# light_digital_sensor.net
KiCad netlist of a schematic drawn in EAGLE
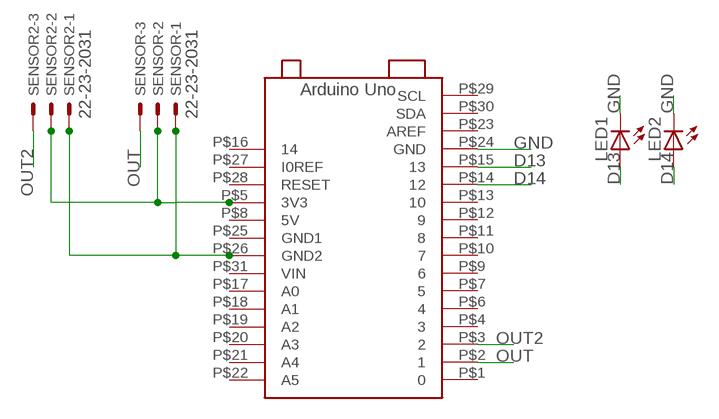
[diagram p0: schematic, sheet 1]

(export (version "E")
  (design (tool "Eeschema 10.0.6"))
  (components
    (comp (ref "LED1")
      (value "LED3MM")
      (footprint "eagle-import:LED3MM")
      (libsource (lib "eagle-import") (part "LED3MM"))
    )
    (comp (ref "LED2")
      (value "LED3MM")
      (footprint "eagle-import:LED3MM")
      (libsource (lib "eagle-import") (part "LED3MM"))
    )
    (comp (ref "SENSOR")
      (value "22-23-2031")
      (footprint "eagle-import:22-23-2031")
      (fields (field (name "MF") "MOLEX"))
      (libsource (lib "eagle-import") (part "22-23-2031"))
    )
    (comp (ref "SENSOR2")
      (value "22-23-2031")
      (footprint "eagle-import:22-23-2031")
      (fields (field (name "MF") "MOLEX"))
      (libsource (lib "eagle-import") (part "22-23-2031"))
    )
    (comp (ref "U$1")
      (value "ARD_UNO")
      (footprint "eagle-import:ARD_UNO")
      (libsource (lib "eagle-import") (part "ARD_UNO"))
    )
  )
  (nets
    (net (code "1") (name "/D13") (class "Default")
      (node (ref "LED1") (pin "A") (pinfunction "A_A") (pintype "passive"))
      (node (ref "U$1") (pin "P$15") (pinfunction "13_P$15") (pintype "bidirectional"))
    )
    (net (code "2") (name "/D14") (class "Default")
      (node (ref "LED2") (pin "A") (pinfunction "A_A") (pintype "passive"))
      (node (ref "U$1") (pin "P$14") (pinfunction "12_P$14") (pintype "bidirectional"))
    )
    (net (code "3") (name "/GND") (class "Default")
      (node (ref "LED1") (pin "K") (pinfunction "C_K") (pintype "passive"))
      (node (ref "LED2") (pin "K") (pinfunction "C_K") (pintype "passive"))
      (node (ref "U$1") (pin "P$24") (pinfunction "GND_P$24") (pintype "bidirectional"))
    )
    (net (code "4") (name "/OUT") (class "Default")
      (node (ref "SENSOR") (pin "3") (pinfunction "S_3") (pintype "passive"))
      (node (ref "U$1") (pin "P$2") (pinfunction "1_P$2") (pintype "bidirectional"))
    )
    (net (code "5") (name "/OUT2") (class "Default")
      (node (ref "SENSOR2") (pin "3") (pinfunction "S_3") (pintype "passive"))
      (node (ref "U$1") (pin "P$3") (pinfunction "2_P$3") (pintype "bidirectional"))
    )
    (net (code "6") (name "Net-(SENSOR2A-S)") (class "Default")
      (node (ref "SENSOR") (pin "1") (pinfunction "S_1") (pintype "passive"))
      (node (ref "SENSOR") (pin "2") (pinfunction "S_2") (pintype "passive"))
      (node (ref "SENSOR2") (pin "1") (pinfunction "S_1") (pintype "passive"))
      (node (ref "SENSOR2") (pin "2") (pinfunction "S_2") (pintype "passive"))
      (node (ref "U$1") (pin "P$26") (pinfunction "GND2_P$26") (pintype "bidirectional"))
      (node (ref "U$1") (pin "P$5") (pinfunction "3V3_P$5") (pintype "bidirectional"))
    )
    (net (code "7") (name "unconnected-(U$1-0-PadP$1)") (class "Default")
      (node (ref "U$1") (pin "P$1") (pinfunction "0_P$1") (pintype "bidirectional"))
    )
    (net (code "8") (name "unconnected-(U$1-3-PadP$4)") (class "Default")
      (node (ref "U$1") (pin "P$4") (pinfunction "3_P$4") (pintype "bidirectional"))
    )
    (net (code "9") (name "unconnected-(U$1-4-PadP$6)") (class "Default")
      (node (ref "U$1") (pin "P$6") (pinfunction "4_P$6") (pintype "bidirectional"))
    )
    (net (code "10") (name "unconnected-(U$1-5-PadP$7)") (class "Default")
      (node (ref "U$1") (pin "P$7") (pinfunction "5_P$7") (pintype "bidirectional"))
    )
    (net (code "11") (name "unconnected-(U$1-5V-PadP$8)") (class "Default")
      (node (ref "U$1") (pin "P$8") (pinfunction "5V_P$8") (pintype "bidirectional"))
    )
    (net (code "12") (name "unconnected-(U$1-6-PadP$9)") (class "Default")
      (node (ref "U$1") (pin "P$9") (pinfunction "6_P$9") (pintype "bidirectional"))
    )
    (net (code "13") (name "unconnected-(U$1-7-PadP$10)") (class "Default")
      (node (ref "U$1") (pin "P$10") (pinfunction "7_P$10") (pintype "bidirectional"))
    )
    (net (code "14") (name "unconnected-(U$1-8-PadP$11)") (class "Default")
      (node (ref "U$1") (pin "P$11") (pinfunction "8_P$11") (pintype "bidirectional"))
    )
    (net (code "15") (name "unconnected-(U$1-9-PadP$12)") (class "Default")
      (node (ref "U$1") (pin "P$12") (pinfunction "9_P$12") (pintype "bidirectional"))
    )
    (net (code "16") (name "unconnected-(U$1-10-PadP$13)") (class "Default")
      (node (ref "U$1") (pin "P$13") (pinfunction "10_P$13") (pintype "bidirectional"))
    )
    (net (code "17") (name "unconnected-(U$1-14-PadP$16)") (class "Default")
      (node (ref "U$1") (pin "P$16") (pinfunction "14_P$16") (pintype "bidirectional"))
    )
    (net (code "18") (name "unconnected-(U$1-A0-PadP$17)") (class "Default")
      (node (ref "U$1") (pin "P$17") (pinfunction "A0_P$17") (pintype "bidirectional"))
    )
    (net (code "19") (name "unconnected-(U$1-A1-PadP$18)") (class "Default")
      (node (ref "U$1") (pin "P$18") (pinfunction "A1_P$18") (pintype "bidirectional"))
    )
    (net (code "20") (name "unconnected-(U$1-A2-PadP$19)") (class "Default")
      (node (ref "U$1") (pin "P$19") (pinfunction "A2_P$19") (pintype "bidirectional"))
    )
    (net (code "21") (name "unconnected-(U$1-A3-PadP$20)") (class "Default")
      (node (ref "U$1") (pin "P$20") (pinfunction "A3_P$20") (pintype "bidirectional"))
    )
    (net (code "22") (name "unconnected-(U$1-A4-PadP$21)") (class "Default")
      (node (ref "U$1") (pin "P$21") (pinfunction "A4_P$21") (pintype "bidirectional"))
    )
    (net (code "23") (name "unconnected-(U$1-A5-PadP$22)") (class "Default")
      (node (ref "U$1") (pin "P$22") (pinfunction "A5_P$22") (pintype "bidirectional"))
    )
    (net (code "24") (name "unconnected-(U$1-AREF-PadP$23)") (class "Default")
      (node (ref "U$1") (pin "P$23") (pinfunction "AREF_P$23") (pintype "bidirectional"))
    )
    (net (code "25") (name "unconnected-(U$1-GND1-PadP$25)") (class "Default")
      (node (ref "U$1") (pin "P$25") (pinfunction "GND1_P$25") (pintype "bidirectional"))
    )
    (net (code "26") (name "unconnected-(U$1-I0REF-PadP$27)") (class "Default")
      (node (ref "U$1") (pin "P$27") (pinfunction "I0REF_P$27") (pintype "bidirectional"))
    )
    (net (code "27") (name "unconnected-(U$1-RESET-PadP$28)") (class "Default")
      (node (ref "U$1") (pin "P$28") (pinfunction "RESET_P$28") (pintype "bidirectional"))
    )
    (net (code "28") (name "unconnected-(U$1-SCL-PadP$29)") (class "Default")
      (node (ref "U$1") (pin "P$29") (pinfunction "SCL_P$29") (pintype "bidirectional"))
    )
    (net (code "29") (name "unconnected-(U$1-SDA-PadP$30)") (class "Default")
      (node (ref "U$1") (pin "P$30") (pinfunction "SDA_P$30") (pintype "bidirectional"))
    )
    (net (code "30") (name "unconnected-(U$1-VIN-PadP$31)") (class "Default")
      (node (ref "U$1") (pin "P$31") (pinfunction "VIN_P$31") (pintype "bidirectional"))
    )
  )
)
